# LED_matrix.net
KiCad netlist of a schematic drawn in Altium Designer
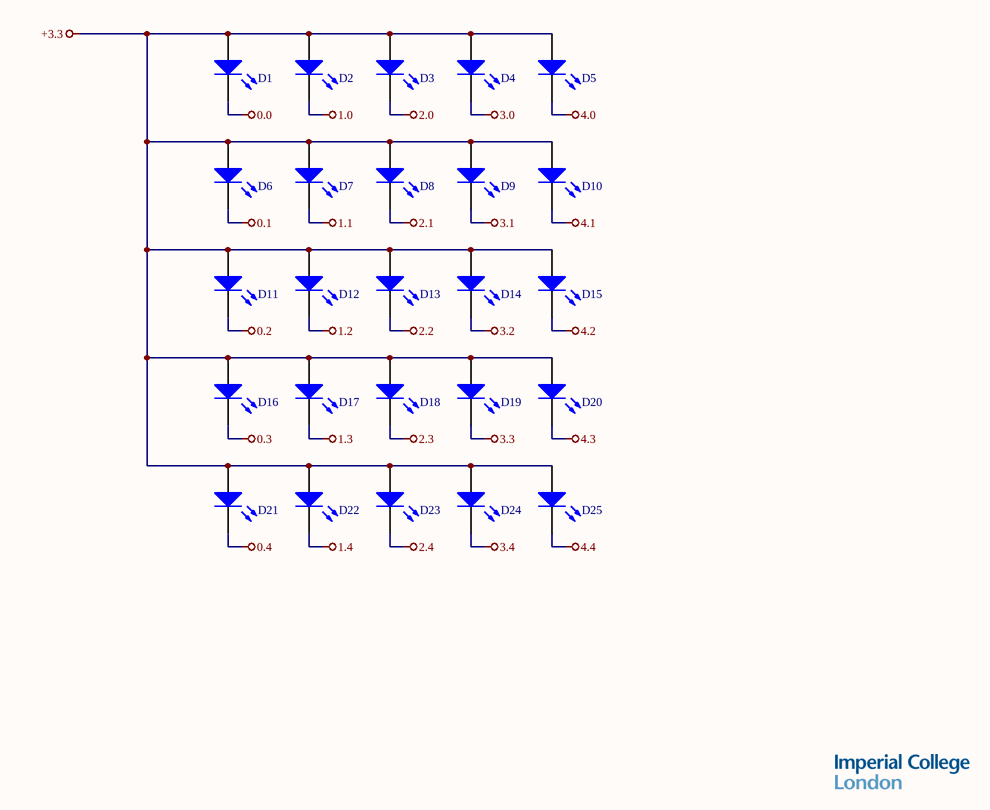
[diagram p0: LED matrix.SchDoc]

(export (version "E")
  (design (tool "Eeschema 10.0.6"))
  (components
    (comp (ref "D1")
      (value "LED")
      (footprint "PCBComponent_1 - duplicate")
      (description "L-793SRD-E, Round Series Red LED, 640 nm 8 mm, Round Lens Through Hole package")
      (libsource (lib "CommunityVault") (part "SYM-c7440e1cac271883-1"))
    )
    (comp (ref "D2")
      (value "LED")
      (footprint "PCBComponent_1 - duplicate")
      (description "L-793SRD-E, Round Series Red LED, 640 nm 8 mm, Round Lens Through Hole package")
      (libsource (lib "CommunityVault") (part "SYM-c7440e1cac271883-1"))
    )
    (comp (ref "D3")
      (value "LED")
      (footprint "PCBComponent_1 - duplicate")
      (description "L-793SRD-E, Round Series Red LED, 640 nm 8 mm, Round Lens Through Hole package")
      (libsource (lib "CommunityVault") (part "SYM-c7440e1cac271883-1"))
    )
    (comp (ref "D4")
      (value "LED")
      (footprint "PCBComponent_1 - duplicate")
      (description "L-793SRD-E, Round Series Red LED, 640 nm 8 mm, Round Lens Through Hole package")
      (libsource (lib "CommunityVault") (part "SYM-c7440e1cac271883-1"))
    )
    (comp (ref "D5")
      (value "LED")
      (footprint "PCBComponent_1 - duplicate")
      (description "L-793SRD-E, Round Series Red LED, 640 nm 8 mm, Round Lens Through Hole package")
      (libsource (lib "CommunityVault") (part "SYM-c7440e1cac271883-1"))
    )
    (comp (ref "D6")
      (value "LED")
      (footprint "PCBComponent_1 - duplicate")
      (description "L-793SRD-E, Round Series Red LED, 640 nm 8 mm, Round Lens Through Hole package")
      (libsource (lib "CommunityVault") (part "SYM-c7440e1cac271883-1"))
    )
    (comp (ref "D7")
      (value "LED")
      (footprint "PCBComponent_1 - duplicate")
      (description "L-793SRD-E, Round Series Red LED, 640 nm 8 mm, Round Lens Through Hole package")
      (libsource (lib "CommunityVault") (part "SYM-c7440e1cac271883-1"))
    )
    (comp (ref "D8")
      (value "LED")
      (footprint "PCBComponent_1 - duplicate")
      (description "L-793SRD-E, Round Series Red LED, 640 nm 8 mm, Round Lens Through Hole package")
      (libsource (lib "CommunityVault") (part "SYM-c7440e1cac271883-1"))
    )
    (comp (ref "D9")
      (value "LED")
      (footprint "PCBComponent_1 - duplicate")
      (description "L-793SRD-E, Round Series Red LED, 640 nm 8 mm, Round Lens Through Hole package")
      (libsource (lib "CommunityVault") (part "SYM-c7440e1cac271883-1"))
    )
    (comp (ref "D10")
      (value "LED")
      (footprint "PCBComponent_1 - duplicate")
      (description "L-793SRD-E, Round Series Red LED, 640 nm 8 mm, Round Lens Through Hole package")
      (libsource (lib "CommunityVault") (part "SYM-c7440e1cac271883-1"))
    )
    (comp (ref "D11")
      (value "LED")
      (footprint "PCBComponent_1 - duplicate")
      (description "L-793SRD-E, Round Series Red LED, 640 nm 8 mm, Round Lens Through Hole package")
      (libsource (lib "CommunityVault") (part "SYM-c7440e1cac271883-1"))
    )
    (comp (ref "D12")
      (value "LED")
      (footprint "PCBComponent_1 - duplicate")
      (description "L-793SRD-E, Round Series Red LED, 640 nm 8 mm, Round Lens Through Hole package")
      (libsource (lib "CommunityVault") (part "SYM-c7440e1cac271883-1"))
    )
    (comp (ref "D13")
      (value "LED")
      (footprint "PCBComponent_1 - duplicate")
      (description "L-793SRD-E, Round Series Red LED, 640 nm 8 mm, Round Lens Through Hole package")
      (libsource (lib "CommunityVault") (part "SYM-c7440e1cac271883-1"))
    )
    (comp (ref "D14")
      (value "LED")
      (footprint "PCBComponent_1 - duplicate")
      (description "L-793SRD-E, Round Series Red LED, 640 nm 8 mm, Round Lens Through Hole package")
      (libsource (lib "CommunityVault") (part "SYM-c7440e1cac271883-1"))
    )
    (comp (ref "D15")
      (value "LED")
      (footprint "PCBComponent_1 - duplicate")
      (description "L-793SRD-E, Round Series Red LED, 640 nm 8 mm, Round Lens Through Hole package")
      (libsource (lib "CommunityVault") (part "SYM-c7440e1cac271883-1"))
    )
    (comp (ref "D16")
      (value "LED")
      (footprint "PCBComponent_1 - duplicate")
      (description "L-793SRD-E, Round Series Red LED, 640 nm 8 mm, Round Lens Through Hole package")
      (libsource (lib "CommunityVault") (part "SYM-c7440e1cac271883-1"))
    )
    (comp (ref "D17")
      (value "LED")
      (footprint "PCBComponent_1 - duplicate")
      (description "L-793SRD-E, Round Series Red LED, 640 nm 8 mm, Round Lens Through Hole package")
      (libsource (lib "CommunityVault") (part "SYM-c7440e1cac271883-1"))
    )
    (comp (ref "D18")
      (value "LED")
      (footprint "PCBComponent_1 - duplicate")
      (description "L-793SRD-E, Round Series Red LED, 640 nm 8 mm, Round Lens Through Hole package")
      (libsource (lib "CommunityVault") (part "SYM-c7440e1cac271883-1"))
    )
    (comp (ref "D19")
      (value "LED")
      (footprint "PCBComponent_1 - duplicate")
      (description "L-793SRD-E, Round Series Red LED, 640 nm 8 mm, Round Lens Through Hole package")
      (libsource (lib "CommunityVault") (part "SYM-c7440e1cac271883-1"))
    )
    (comp (ref "D20")
      (value "LED")
      (footprint "PCBComponent_1 - duplicate")
      (description "L-793SRD-E, Round Series Red LED, 640 nm 8 mm, Round Lens Through Hole package")
      (libsource (lib "CommunityVault") (part "SYM-c7440e1cac271883-1"))
    )
    (comp (ref "D21")
      (value "LED")
      (footprint "PCBComponent_1 - duplicate")
      (description "L-793SRD-E, Round Series Red LED, 640 nm 8 mm, Round Lens Through Hole package")
      (libsource (lib "CommunityVault") (part "SYM-c7440e1cac271883-1"))
    )
    (comp (ref "D22")
      (value "LED")
      (footprint "PCBComponent_1 - duplicate")
      (description "L-793SRD-E, Round Series Red LED, 640 nm 8 mm, Round Lens Through Hole package")
      (libsource (lib "CommunityVault") (part "SYM-c7440e1cac271883-1"))
    )
    (comp (ref "D23")
      (value "LED")
      (footprint "PCBComponent_1 - duplicate")
      (description "L-793SRD-E, Round Series Red LED, 640 nm 8 mm, Round Lens Through Hole package")
      (libsource (lib "CommunityVault") (part "SYM-c7440e1cac271883-1"))
    )
    (comp (ref "D24")
      (value "LED")
      (footprint "PCBComponent_1 - duplicate")
      (description "L-793SRD-E, Round Series Red LED, 640 nm 8 mm, Round Lens Through Hole package")
      (libsource (lib "CommunityVault") (part "SYM-c7440e1cac271883-1"))
    )
    (comp (ref "D25")
      (value "LED")
      (footprint "PCBComponent_1 - duplicate")
      (description "L-793SRD-E, Round Series Red LED, 640 nm 8 mm, Round Lens Through Hole package")
      (libsource (lib "CommunityVault") (part "SYM-c7440e1cac271883-1"))
    )
  )
  (nets
    (net (code "1") (name "+3.3") (class "Default")
      (node (ref "D1") (pin "1") (pinfunction "A_1") (pintype "passive"))
      (node (ref "D10") (pin "1") (pinfunction "A_1") (pintype "passive"))
      (node (ref "D11") (pin "1") (pinfunction "A_1") (pintype "passive"))
      (node (ref "D12") (pin "1") (pinfunction "A_1") (pintype "passive"))
      (node (ref "D13") (pin "1") (pinfunction "A_1") (pintype "passive"))
      (node (ref "D14") (pin "1") (pinfunction "A_1") (pintype "passive"))
      (node (ref "D15") (pin "1") (pinfunction "A_1") (pintype "passive"))
      (node (ref "D16") (pin "1") (pinfunction "A_1") (pintype "passive"))
      (node (ref "D17") (pin "1") (pinfunction "A_1") (pintype "passive"))
      (node (ref "D18") (pin "1") (pinfunction "A_1") (pintype "passive"))
      (node (ref "D19") (pin "1") (pinfunction "A_1") (pintype "passive"))
      (node (ref "D2") (pin "1") (pinfunction "A_1") (pintype "passive"))
      (node (ref "D20") (pin "1") (pinfunction "A_1") (pintype "passive"))
      (node (ref "D21") (pin "1") (pinfunction "A_1") (pintype "passive"))
      (node (ref "D22") (pin "1") (pinfunction "A_1") (pintype "passive"))
      (node (ref "D23") (pin "1") (pinfunction "A_1") (pintype "passive"))
      (node (ref "D24") (pin "1") (pinfunction "A_1") (pintype "passive"))
      (node (ref "D25") (pin "1") (pinfunction "A_1") (pintype "passive"))
      (node (ref "D3") (pin "1") (pinfunction "A_1") (pintype "passive"))
      (node (ref "D4") (pin "1") (pinfunction "A_1") (pintype "passive"))
      (node (ref "D5") (pin "1") (pinfunction "A_1") (pintype "passive"))
      (node (ref "D6") (pin "1") (pinfunction "A_1") (pintype "passive"))
      (node (ref "D7") (pin "1") (pinfunction "A_1") (pintype "passive"))
      (node (ref "D8") (pin "1") (pinfunction "A_1") (pintype "passive"))
      (node (ref "D9") (pin "1") (pinfunction "A_1") (pintype "passive"))
    )
    (net (code "2") (name "0.0") (class "Default")
      (node (ref "D1") (pin "2") (pinfunction "K_2") (pintype "passive"))
    )
    (net (code "3") (name "0.1") (class "Default")
      (node (ref "D6") (pin "2") (pinfunction "K_2") (pintype "passive"))
    )
    (net (code "4") (name "0.2") (class "Default")
      (node (ref "D11") (pin "2") (pinfunction "K_2") (pintype "passive"))
    )
    (net (code "5") (name "0.3") (class "Default")
      (node (ref "D16") (pin "2") (pinfunction "K_2") (pintype "passive"))
    )
    (net (code "6") (name "0.4") (class "Default")
      (node (ref "D21") (pin "2") (pinfunction "K_2") (pintype "passive"))
    )
    (net (code "7") (name "1.0") (class "Default")
      (node (ref "D2") (pin "2") (pinfunction "K_2") (pintype "passive"))
    )
    (net (code "8") (name "1.1") (class "Default")
      (node (ref "D7") (pin "2") (pinfunction "K_2") (pintype "passive"))
    )
    (net (code "9") (name "1.2") (class "Default")
      (node (ref "D12") (pin "2") (pinfunction "K_2") (pintype "passive"))
    )
    (net (code "10") (name "1.3") (class "Default")
      (node (ref "D17") (pin "2") (pinfunction "K_2") (pintype "passive"))
    )
    (net (code "11") (name "1.4") (class "Default")
      (node (ref "D22") (pin "2") (pinfunction "K_2") (pintype "passive"))
    )
    (net (code "12") (name "2.0") (class "Default")
      (node (ref "D3") (pin "2") (pinfunction "K_2") (pintype "passive"))
    )
    (net (code "13") (name "2.1") (class "Default")
      (node (ref "D8") (pin "2") (pinfunction "K_2") (pintype "passive"))
    )
    (net (code "14") (name "2.2") (class "Default")
      (node (ref "D13") (pin "2") (pinfunction "K_2") (pintype "passive"))
    )
    (net (code "15") (name "2.3") (class "Default")
      (node (ref "D18") (pin "2") (pinfunction "K_2") (pintype "passive"))
    )
    (net (code "16") (name "2.4") (class "Default")
      (node (ref "D23") (pin "2") (pinfunction "K_2") (pintype "passive"))
    )
    (net (code "17") (name "3.0") (class "Default")
      (node (ref "D4") (pin "2") (pinfunction "K_2") (pintype "passive"))
    )
    (net (code "18") (name "3.1") (class "Default")
      (node (ref "D9") (pin "2") (pinfunction "K_2") (pintype "passive"))
    )
    (net (code "19") (name "3.2") (class "Default")
      (node (ref "D14") (pin "2") (pinfunction "K_2") (pintype "passive"))
    )
    (net (code "20") (name "3.3") (class "Default")
      (node (ref "D19") (pin "2") (pinfunction "K_2") (pintype "passive"))
    )
    (net (code "21") (name "3.4") (class "Default")
      (node (ref "D24") (pin "2") (pinfunction "K_2") (pintype "passive"))
    )
    (net (code "22") (name "4.0") (class "Default")
      (node (ref "D5") (pin "2") (pinfunction "K_2") (pintype "passive"))
    )
    (net (code "23") (name "4.1") (class "Default")
      (node (ref "D10") (pin "2") (pinfunction "K_2") (pintype "passive"))
    )
    (net (code "24") (name "4.2") (class "Default")
      (node (ref "D15") (pin "2") (pinfunction "K_2") (pintype "passive"))
    )
    (net (code "25") (name "4.3") (class "Default")
      (node (ref "D20") (pin "2") (pinfunction "K_2") (pintype "passive"))
    )
    (net (code "26") (name "4.4") (class "Default")
      (node (ref "D25") (pin "2") (pinfunction "K_2") (pintype "passive"))
    )
  )
)
